# behind_v1_0.net
KiCad netlist of a schematic drawn in Altium Designer
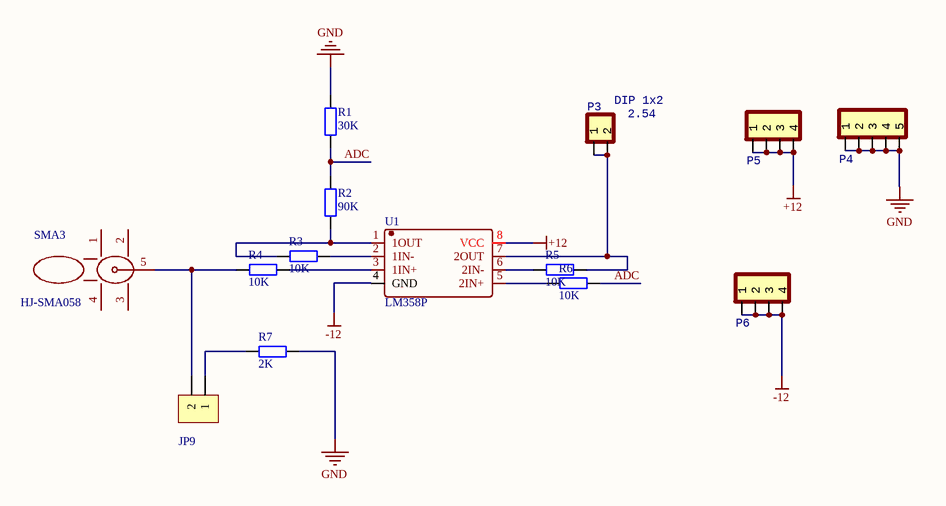
[diagram p0: behind_v1.0.SchDoc]

(export (version "E")
  (design (tool "Eeschema 10.0.6"))
  (components
    (comp (ref "JP9")
      (value "HDR-1X2")
      (footprint "KF301-5.0-2P")
      (description "2P接插件")
      (fields (field (name "版权归属") "源创客"))
      (libsource (lib "4.9   - 接插件-脚距5.0") (part "Header 2"))
    )
    (comp (ref "P3")
      (value "2.54")
      (footprint "HDR1X2_2.54_180")
      (description "Header")
      (fields (field (name "TYPE") "DIP 1x2") (field (name "Comment") "DIP 1x2"))
      (libsource (lib "adlib") (part "HDR1x2_2.54"))
    )
    (comp (ref "P4")
      (value "HDR1x5_2.54")
      (footprint "HDR1X5_2.54_180")
      (description "Header")
      (libsource (lib "adlib") (part "HDR1x5_2.54"))
    )
    (comp (ref "P5")
      (value "HDR1x4_2.54")
      (footprint "HDR1x4_2.54_180")
      (description "Header")
      (libsource (lib "adlib") (part "HDR1x4_2.54"))
    )
    (comp (ref "P6")
      (value "HDR1x4_2.54")
      (footprint "HDR1x4_2.54_180")
      (description "Header")
      (libsource (lib "adlib") (part "HDR1x4_2.54"))
    )
    (comp (ref "R1")
      (value "30K")
      (footprint "RS 1/4W")
      (description "直插色环电阻")
      (fields (field (name "版权归属") "源创客"))
      (libsource (lib "3.1   - 电阻-电容-电感") (part "R-CRR"))
    )
    (comp (ref "R2")
      (value "90K")
      (footprint "RS 1/4W")
      (description "直插色环电阻")
      (fields (field (name "版权归属") "源创客"))
      (libsource (lib "3.1   - 电阻-电容-电感") (part "R-CRR"))
    )
    (comp (ref "R3")
      (value "10K")
      (footprint "RS 1/4W")
      (description "直插色环电阻")
      (fields (field (name "版权归属") "源创客"))
      (libsource (lib "3.1   - 电阻-电容-电感") (part "R-CRR"))
    )
    (comp (ref "R4")
      (value "10K")
      (footprint "RS 1/4W")
      (description "直插色环电阻")
      (fields (field (name "版权归属") "源创客"))
      (libsource (lib "3.1   - 电阻-电容-电感") (part "R-CRR"))
    )
    (comp (ref "R5")
      (value "10K")
      (footprint "RS 1/4W")
      (description "直插色环电阻")
      (fields (field (name "版权归属") "源创客"))
      (libsource (lib "3.1   - 电阻-电容-电感") (part "R-CRR"))
    )
    (comp (ref "R6")
      (value "10K")
      (footprint "RS 1/4W")
      (description "直插色环电阻")
      (fields (field (name "版权归属") "源创客"))
      (libsource (lib "3.1   - 电阻-电容-电感") (part "R-CRR"))
    )
    (comp (ref "R7")
      (value "2K")
      (footprint "RS 1/4W")
      (description "直插色环电阻")
      (fields (field (name "版权归属") "源创客"))
      (libsource (lib "3.1   - 电阻-电容-电感") (part "R-CRR"))
    )
    (comp (ref "SMA3")
      (value "HJ-SMA058")
      (footprint "HJ-SMA058")
      (libsource (lib "chw_2020") (part "HJ-SMA058"))
    )
    (comp (ref "U1") (value "LM358P") (footprint "LM358P") (libsource (lib "chw_2020") (part "LM358P")))
  )
  (nets
    (net (code "1") (name "+12") (class "Default")
      (node (ref "P5") (pin "1") (pinfunction "1_1") (pintype "passive"))
      (node (ref "P5") (pin "2") (pinfunction "2_2") (pintype "passive"))
      (node (ref "P5") (pin "3") (pinfunction "3_3") (pintype "passive"))
      (node (ref "P5") (pin "4") (pinfunction "4_4") (pintype "passive"))
      (node (ref "U1") (pin "8") (pinfunction "VCC_8") (pintype "passive"))
    )
    (net (code "2") (name "-12") (class "Default")
      (node (ref "P6") (pin "1") (pinfunction "1_1") (pintype "passive"))
      (node (ref "P6") (pin "2") (pinfunction "2_2") (pintype "passive"))
      (node (ref "P6") (pin "3") (pinfunction "3_3") (pintype "passive"))
      (node (ref "P6") (pin "4") (pinfunction "4_4") (pintype "passive"))
      (node (ref "U1") (pin "4") (pinfunction "GND_4") (pintype "passive"))
    )
    (net (code "3") (name "/ADC") (class "Default")
      (node (ref "R1") (pin "1") (pinfunction "1_1") (pintype "passive"))
      (node (ref "R2") (pin "2") (pinfunction "2_2") (pintype "passive"))
      (node (ref "R6") (pin "2") (pinfunction "2_2") (pintype "passive"))
    )
    (net (code "4") (name "GND") (class "Default")
      (node (ref "P4") (pin "1") (pinfunction "1_1") (pintype "passive"))
      (node (ref "P4") (pin "2") (pinfunction "2_2") (pintype "passive"))
      (node (ref "P4") (pin "3") (pinfunction "3_3") (pintype "passive"))
      (node (ref "P4") (pin "4") (pinfunction "4_4") (pintype "passive"))
      (node (ref "P4") (pin "5") (pinfunction "5_5") (pintype "passive"))
      (node (ref "R1") (pin "2") (pinfunction "2_2") (pintype "passive"))
      (node (ref "R7") (pin "2") (pinfunction "2_2") (pintype "passive"))
    )
    (net (code "5") (name "Net-(JP9-Pad1)") (class "Default")
      (node (ref "JP9") (pin "1") (pinfunction "1_1") (pintype "passive"))
      (node (ref "R7") (pin "1") (pinfunction "1_1") (pintype "passive"))
    )
    (net (code "6") (name "Net-(JP9-Pad2)") (class "Default")
      (node (ref "JP9") (pin "2") (pinfunction "2_2") (pintype "passive"))
      (node (ref "R4") (pin "1") (pinfunction "1_1") (pintype "passive"))
      (node (ref "SMA3") (pin "5") (pinfunction "5_5") (pintype "passive"))
    )
    (net (code "7") (name "Net-(U1-1IN+)") (class "Default")
      (node (ref "R4") (pin "2") (pinfunction "2_2") (pintype "passive"))
      (node (ref "U1") (pin "3") (pinfunction "1IN+_3") (pintype "passive"))
    )
    (net (code "8") (name "Net-(U1-1IN-)") (class "Default")
      (node (ref "R3") (pin "2") (pinfunction "2_2") (pintype "passive"))
      (node (ref "U1") (pin "2") (pinfunction "1IN-_2") (pintype "passive"))
    )
    (net (code "9") (name "Net-(U1-1OUT)") (class "Default")
      (node (ref "R2") (pin "1") (pinfunction "1_1") (pintype "passive"))
      (node (ref "R3") (pin "1") (pinfunction "1_1") (pintype "passive"))
      (node (ref "U1") (pin "1") (pinfunction "1OUT_1") (pintype "passive"))
    )
    (net (code "10") (name "Net-(U1-2IN+)") (class "Default")
      (node (ref "R6") (pin "1") (pinfunction "1_1") (pintype "passive"))
      (node (ref "U1") (pin "5") (pinfunction "2IN+_5") (pintype "passive"))
    )
    (net (code "11") (name "Net-(U1-2IN-)") (class "Default")
      (node (ref "R5") (pin "1") (pinfunction "1_1") (pintype "passive"))
      (node (ref "U1") (pin "6") (pinfunction "2IN-_6") (pintype "passive"))
    )
    (net (code "12") (name "Net-(U1-2OUT)") (class "Default")
      (node (ref "P3") (pin "1") (pinfunction "1_1") (pintype "passive"))
      (node (ref "P3") (pin "2") (pinfunction "2_2") (pintype "passive"))
      (node (ref "R5") (pin "2") (pinfunction "2_2") (pintype "passive"))
      (node (ref "U1") (pin "7") (pinfunction "2OUT_7") (pintype "passive"))
    )
    (net (code "13") (name "unconnected-(SMA3-Pad1)") (class "Default")
      (node (ref "SMA3") (pin "1") (pinfunction "1_1") (pintype "passive"))
    )
    (net (code "14") (name "unconnected-(SMA3-Pad2)") (class "Default")
      (node (ref "SMA3") (pin "2") (pinfunction "2_2") (pintype "passive"))
    )
    (net (code "15") (name "unconnected-(SMA3-Pad3)") (class "Default")
      (node (ref "SMA3") (pin "3") (pinfunction "3_3") (pintype "passive"))
    )
    (net (code "16") (name "unconnected-(SMA3-Pad4)") (class "Default")
      (node (ref "SMA3") (pin "4") (pinfunction "4_4") (pintype "passive"))
    )
  )
)
